# Laser_Array_CPU_V1_2.net
KiCad netlist of a schematic drawn in EAGLE
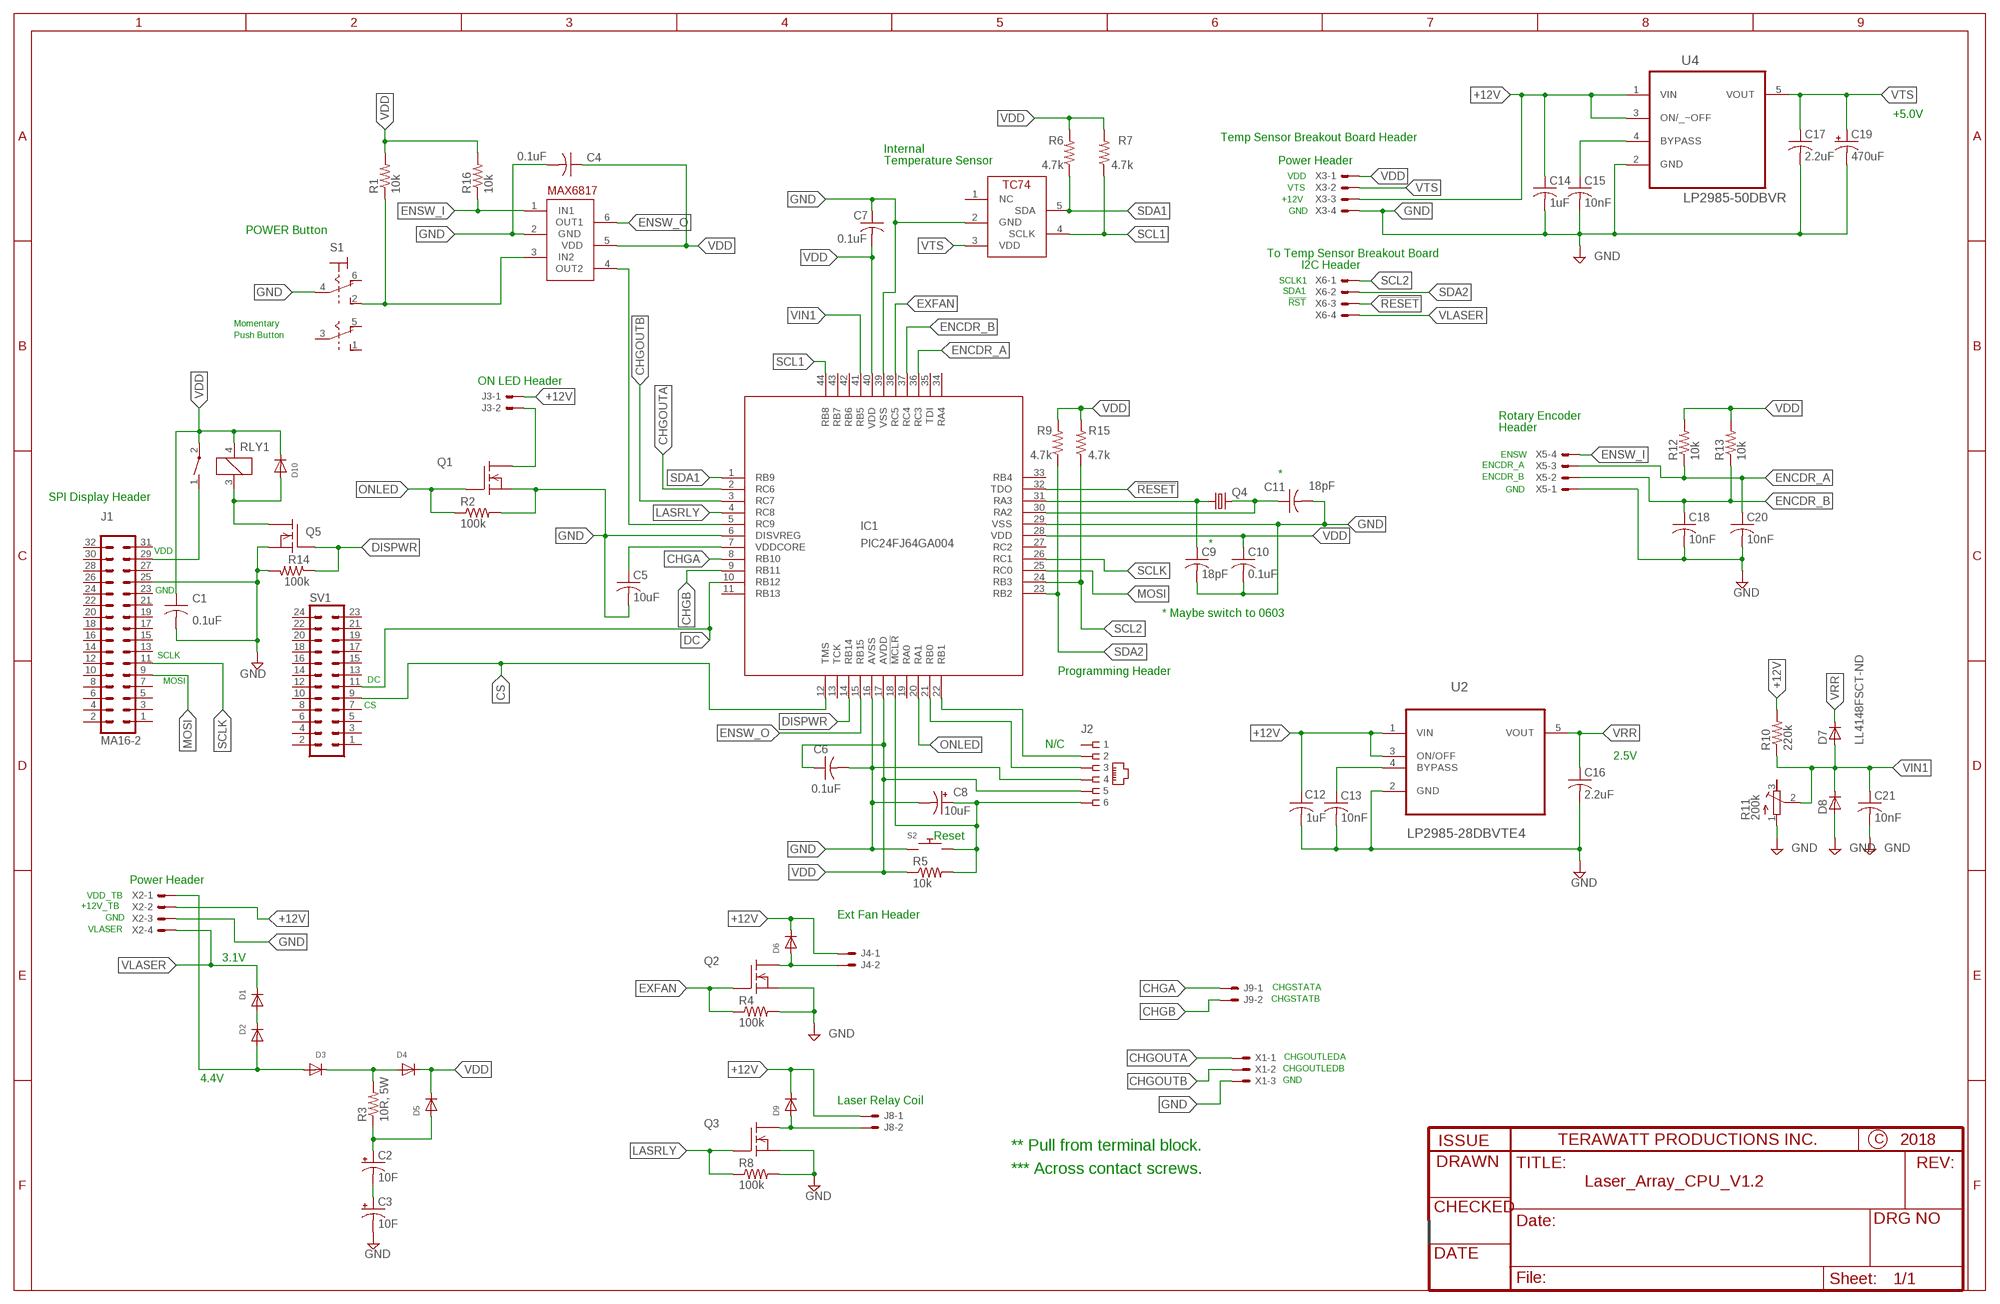
[diagram p0: schematic, sheet 1]

(export (version "E")
  (design (tool "Eeschema 10.0.6"))
  (components
    (comp (ref "C1")
      (value "0.1uF")
      (footprint "eagle-import:C0805")
      (libsource (lib "eagle-import") (part "C-USC0805"))
    )
    (comp (ref "C2")
      (value "10F")
      (footprint "eagle-import:E5-10,5")
      (libsource (lib "eagle-import") (part "CPOL-USE5-10.5"))
    )
    (comp (ref "C3")
      (value "10F")
      (footprint "eagle-import:E5-10,5")
      (libsource (lib "eagle-import") (part "CPOL-USE5-10.5"))
    )
    (comp (ref "C4")
      (value "0.1uF")
      (footprint "eagle-import:C0805")
      (libsource (lib "eagle-import") (part "C-USC0805"))
    )
    (comp (ref "C5")
      (value "10uF")
      (footprint "eagle-import:C0805")
      (libsource (lib "eagle-import") (part "C-USC0805"))
    )
    (comp (ref "C6")
      (value "0.1uF")
      (footprint "eagle-import:C0805")
      (libsource (lib "eagle-import") (part "C-USC0805"))
    )
    (comp (ref "C7")
      (value "0.1uF")
      (footprint "eagle-import:C0805")
      (libsource (lib "eagle-import") (part "C-USC0805"))
    )
    (comp (ref "C8")
      (value "10uF")
      (footprint "eagle-import:CAP3X3")
      (libsource (lib "eagle-import") (part "CAP3X3"))
    )
    (comp (ref "C9")
      (value "18pF")
      (footprint "eagle-import:C0805")
      (libsource (lib "eagle-import") (part "C-USC0805"))
    )
    (comp (ref "C10")
      (value "0.1uF")
      (footprint "eagle-import:C0805")
      (libsource (lib "eagle-import") (part "C-USC0805"))
    )
    (comp (ref "C11")
      (value "18pF")
      (footprint "eagle-import:C0805")
      (libsource (lib "eagle-import") (part "C-USC0805"))
    )
    (comp (ref "C12")
      (value "1uF")
      (footprint "eagle-import:C0805")
      (libsource (lib "eagle-import") (part "C-USC0805"))
    )
    (comp (ref "C13")
      (value "10nF")
      (footprint "eagle-import:C0805")
      (libsource (lib "eagle-import") (part "C-USC0805"))
    )
    (comp (ref "C14")
      (value "1uF")
      (footprint "eagle-import:C0805")
      (libsource (lib "eagle-import") (part "C-USC0805"))
    )
    (comp (ref "C15")
      (value "10nF")
      (footprint "eagle-import:C0805")
      (libsource (lib "eagle-import") (part "C-USC0805"))
    )
    (comp (ref "C16")
      (value "2.2uF")
      (footprint "eagle-import:C0805")
      (libsource (lib "eagle-import") (part "C-USC0805"))
    )
    (comp (ref "C17")
      (value "2.2uF")
      (footprint "eagle-import:C0805")
      (libsource (lib "eagle-import") (part "C-USC0805"))
    )
    (comp (ref "C18")
      (value "10nF")
      (footprint "eagle-import:C0805")
      (libsource (lib "eagle-import") (part "C-USC0805"))
    )
    (comp (ref "C19")
      (value "470uF")
      (footprint "eagle-import:PANASONIC_F")
      (libsource (lib "eagle-import") (part "CPOL-USF"))
    )
    (comp (ref "C20")
      (value "10nF")
      (footprint "eagle-import:C0805")
      (libsource (lib "eagle-import") (part "C-USC0805"))
    )
    (comp (ref "C21")
      (value "10nF")
      (footprint "eagle-import:C0805")
      (libsource (lib "eagle-import") (part "C-USC0805"))
    )
    (comp (ref "D1")
      (value "S10M-TPMSCT_ND")
      (footprint "eagle-import:S10M-TPMSCT-ND")
      (libsource (lib "eagle-import") (part "S10M-TPMSCT_ND"))
    )
    (comp (ref "D2")
      (value "S10M-TPMSCT_ND")
      (footprint "eagle-import:S10M-TPMSCT-ND")
      (libsource (lib "eagle-import") (part "S10M-TPMSCT_ND"))
    )
    (comp (ref "D3")
      (value "S10M-TPMSCT_ND")
      (footprint "eagle-import:S10M-TPMSCT-ND")
      (libsource (lib "eagle-import") (part "S10M-TPMSCT_ND"))
    )
    (comp (ref "D4")
      (value "DIODE_GENPURP_1A_100V")
      (footprint "eagle-import:DO214AC")
      (libsource (lib "eagle-import") (part "DIODE_GENPURP_1A_100V"))
    )
    (comp (ref "D5")
      (value "DIODE_GENPURP_1A_100V")
      (footprint "eagle-import:DO214AC")
      (libsource (lib "eagle-import") (part "DIODE_GENPURP_1A_100V"))
    )
    (comp (ref "D6")
      (value "DIODE_GENPURP_1A_100V")
      (footprint "eagle-import:DO214AC")
      (libsource (lib "eagle-import") (part "DIODE_GENPURP_1A_100V"))
    )
    (comp (ref "D7")
      (value "LL4148FSCT-ND")
      (footprint "eagle-import:SOD80")
      (libsource (lib "eagle-import") (part "D-SOD-80"))
    )
    (comp (ref "D8")
      (value "LL4148FSCT-ND")
      (footprint "eagle-import:SOD80")
      (libsource (lib "eagle-import") (part "D-SOD-80"))
    )
    (comp (ref "D9")
      (value "DIODE_GENPURP_1A_100V")
      (footprint "eagle-import:DO214AC")
      (libsource (lib "eagle-import") (part "DIODE_GENPURP_1A_100V"))
    )
    (comp (ref "D10")
      (value "DIODE_GENPURP_1A_100V")
      (footprint "eagle-import:DO214AC")
      (libsource (lib "eagle-import") (part "DIODE_GENPURP_1A_100V"))
    )
    (comp (ref "IC1")
      (value "PIC24FJ64GA004")
      (footprint "eagle-import:TQFP44")
      (fields (field (name "MPN") "PIC24FJ64GA004-E/PT"))
      (libsource (lib "eagle-import") (part "PIC24FJ64GA004"))
    )
    (comp (ref "J1")
      (value "MA16-2")
      (footprint "eagle-import:MA16-2")
      (libsource (lib "eagle-import") (part "MA16-2"))
    )
    (comp (ref "J2")
      (value "RJ_25")
      (footprint "eagle-import:RJ11-NO_SHIELD")
      (libsource (lib "eagle-import") (part "RJ_25"))
    )
    (comp (ref "J3")
      (value "22-23-2021")
      (footprint "eagle-import:22-23-2021")
      (fields (field (name "MF") "MOLEX"))
      (libsource (lib "eagle-import") (part "22-23-2021"))
    )
    (comp (ref "J4")
      (value "22-23-2021")
      (footprint "eagle-import:22-23-2021")
      (fields (field (name "MF") "MOLEX"))
      (libsource (lib "eagle-import") (part "22-23-2021"))
    )
    (comp (ref "J8")
      (value "22-23-2021")
      (footprint "eagle-import:22-23-2021")
      (fields (field (name "MF") "MOLEX"))
      (libsource (lib "eagle-import") (part "22-23-2021"))
    )
    (comp (ref "J9")
      (value "22-23-2021")
      (footprint "eagle-import:22-23-2021")
      (fields (field (name "MF") "MOLEX"))
      (libsource (lib "eagle-import") (part "22-23-2021"))
    )
    (comp (ref "Q1")
      (value "QS5U34CT-ND_MOSFET_N_CHANNEL")
      (footprint "eagle-import:SOT23-5L")
      (libsource (lib "eagle-import") (part "QS5U34CT-ND_MOSFET_N_CHANNEL"))
    )
    (comp (ref "Q2")
      (value "QS5U34CT-ND_MOSFET_N_CHANNEL")
      (footprint "eagle-import:SOT23-5L")
      (libsource (lib "eagle-import") (part "QS5U34CT-ND_MOSFET_N_CHANNEL"))
    )
    (comp (ref "Q3")
      (value "QS5U34CT-ND_MOSFET_N_CHANNEL")
      (footprint "eagle-import:SOT23-5L")
      (libsource (lib "eagle-import") (part "QS5U34CT-ND_MOSFET_N_CHANNEL"))
    )
    (comp (ref "Q4")
      (value "CRYSTALSM49")
      (footprint "eagle-import:SM49")
      (libsource (lib "eagle-import") (part "CRYSTALSM49"))
    )
    (comp (ref "Q5")
      (value "QS5U34CT-ND_MOSFET_N_CHANNEL")
      (footprint "eagle-import:SOT23-5L")
      (libsource (lib "eagle-import") (part "QS5U34CT-ND_MOSFET_N_CHANNEL"))
    )
    (comp (ref "R1")
      (value "10k")
      (footprint "eagle-import:R0805")
      (libsource (lib "eagle-import") (part "R-US_R0805"))
    )
    (comp (ref "R2")
      (value "100k")
      (footprint "eagle-import:R0805")
      (libsource (lib "eagle-import") (part "R-US_R0805"))
    )
    (comp (ref "R3")
      (value "10R, 5W")
      (footprint "eagle-import:RESISTOR5W")
      (libsource (lib "eagle-import") (part "RESISTOR5W"))
    )
    (comp (ref "R4")
      (value "100k")
      (footprint "eagle-import:R0805")
      (libsource (lib "eagle-import") (part "R-US_R0805"))
    )
    (comp (ref "R5")
      (value "10k")
      (footprint "eagle-import:R0805")
      (libsource (lib "eagle-import") (part "R-US_R0805"))
    )
    (comp (ref "R6")
      (value "4.7k")
      (footprint "eagle-import:M0805")
      (libsource (lib "eagle-import") (part "R-US_M0805"))
    )
    (comp (ref "R7")
      (value "4.7k")
      (footprint "eagle-import:M0805")
      (libsource (lib "eagle-import") (part "R-US_M0805"))
    )
    (comp (ref "R8")
      (value "100k")
      (footprint "eagle-import:R0805")
      (libsource (lib "eagle-import") (part "R-US_R0805"))
    )
    (comp (ref "R9")
      (value "4.7k")
      (footprint "eagle-import:M0805")
      (libsource (lib "eagle-import") (part "R-US_M0805"))
    )
    (comp (ref "R10")
      (value "220k")
      (footprint "eagle-import:M0805")
      (libsource (lib "eagle-import") (part "R-US_M0805"))
    )
    (comp (ref "R11")
      (value "200k")
      (footprint "eagle-import:RTRIM3224X")
      (libsource (lib "eagle-import") (part "R-TRIMM3224X"))
    )
    (comp (ref "R12")
      (value "10k")
      (footprint "eagle-import:M0805")
      (libsource (lib "eagle-import") (part "R-US_M0805"))
    )
    (comp (ref "R13")
      (value "10k")
      (footprint "eagle-import:M0805")
      (libsource (lib "eagle-import") (part "R-US_M0805"))
    )
    (comp (ref "R14")
      (value "100k")
      (footprint "eagle-import:R0805")
      (libsource (lib "eagle-import") (part "R-US_R0805"))
    )
    (comp (ref "R15")
      (value "4.7k")
      (footprint "eagle-import:M0805")
      (libsource (lib "eagle-import") (part "R-US_M0805"))
    )
    (comp (ref "R16")
      (value "10k")
      (footprint "eagle-import:R0805")
      (libsource (lib "eagle-import") (part "R-US_R0805"))
    )
    (comp (ref "RLY1")
      (value "RELAY_SPST_1A")
      (footprint "eagle-import:RELAY_SPST_1A")
      (libsource (lib "eagle-import") (part "RELAY_SPST_1A"))
    )
    (comp (ref "S1")
      (value "DPDT_TOGGLE")
      (footprint "eagle-import:22-23-2061")
      (libsource (lib "eagle-import") (part "DPDT_TOGGLE"))
    )
    (comp (ref "S2")
      (value "TACT_PB")
      (footprint "eagle-import:PUSHBUTTON_SMD_SJ")
      (libsource (lib "eagle-import") (part "TACT_PB"))
    )
    (comp (ref "S3")
      (value "TC74")
      (footprint "eagle-import:SOT23-5L")
      (libsource (lib "eagle-import") (part "TC74"))
    )
    (comp (ref "SV1")
      (value "MA12-2")
      (footprint "eagle-import:MA12-2")
      (libsource (lib "eagle-import") (part "MA12-2"))
    )
    (comp (ref "U1")
      (value "MAX6817")
      (footprint "eagle-import:SOT23-6")
      (libsource (lib "eagle-import") (part "MAX6817"))
    )
    (comp (ref "U2")
      (value "LP2985-28DBVTE4")
      (footprint "eagle-import:SOT95P280X145-5N")
      (libsource (lib "eagle-import") (part "LP2985-28DBVTE4"))
    )
    (comp (ref "U4")
      (value "LP2985-50DBVR")
      (footprint "eagle-import:SOT95P280X145-5N")
      (fields (field (name "MPN") "LP2985-33DBVT"))
      (libsource (lib "eagle-import") (part "LP2985-50DBVR"))
    )
    (comp (ref "X1")
      (value "22-23-2031")
      (footprint "eagle-import:22-23-2031")
      (fields (field (name "MF") "MOLEX"))
      (libsource (lib "eagle-import") (part "22-23-2031"))
    )
    (comp (ref "X2")
      (value "22-23-2041")
      (footprint "eagle-import:22-23-2041")
      (fields (field (name "MF") "MOLEX"))
      (libsource (lib "eagle-import") (part "22-23-2041"))
    )
    (comp (ref "X3")
      (value "22-23-2041")
      (footprint "eagle-import:22-23-2041")
      (fields (field (name "MF") "MOLEX"))
      (libsource (lib "eagle-import") (part "22-23-2041"))
    )
    (comp (ref "X5")
      (value "22-23-2041")
      (footprint "eagle-import:22-23-2041")
      (fields (field (name "MF") "MOLEX"))
      (libsource (lib "eagle-import") (part "22-23-2041"))
    )
    (comp (ref "X6")
      (value "22-23-2041")
      (footprint "eagle-import:22-23-2041")
      (fields (field (name "MF") "MOLEX"))
      (libsource (lib "eagle-import") (part "22-23-2041"))
    )
  )
  (nets
    (net (code "1") (name "+12V") (class "Default")
      (node (ref "C12") (pin "1") (pinfunction "1_1") (pintype "passive"))
      (node (ref "C14") (pin "1") (pinfunction "1_1") (pintype "passive"))
      (node (ref "D6") (pin "C") (pinfunction "C_C") (pintype "passive"))
      (node (ref "D9") (pin "C") (pinfunction "C_C") (pintype "passive"))
      (node (ref "J3") (pin "1") (pinfunction "S_1") (pintype "passive"))
      (node (ref "J4") (pin "1") (pinfunction "S_1") (pintype "passive"))
      (node (ref "J8") (pin "1") (pinfunction "S_1") (pintype "passive"))
      (node (ref "R10") (pin "2") (pinfunction "2_2") (pintype "passive"))
      (node (ref "U2") (pin "1") (pinfunction "VIN_1") (pintype "power_in"))
      (node (ref "U2") (pin "3") (pinfunction "ON/OFF_3") (pintype "input"))
      (node (ref "U4") (pin "1") (pinfunction "VIN_1") (pintype "power_in"))
      (node (ref "U4") (pin "3") (pinfunction "ON/_~{OFF}_3") (pintype "input"))
      (node (ref "X2") (pin "2") (pinfunction "S_2") (pintype "passive"))
      (node (ref "X3") (pin "3") (pinfunction "S_3") (pintype "passive"))
    )
    (net (code "2") (name "/~{RESET}") (class "Default")
      (node (ref "IC1") (pin "32") (pinfunction "TDO_32") (pintype "output"))
      (node (ref "X6") (pin "3") (pinfunction "S_3") (pintype "passive"))
    )
    (net (code "3") (name "CHGA") (class "Default")
      (node (ref "IC1") (pin "8") (pinfunction "RB10_8") (pintype "bidirectional"))
      (node (ref "J9") (pin "1") (pinfunction "S_1") (pintype "passive"))
    )
    (net (code "4") (name "CHGB") (class "Default")
      (node (ref "IC1") (pin "9") (pinfunction "RB11_9") (pintype "bidirectional"))
      (node (ref "J9") (pin "2") (pinfunction "S_2") (pintype "passive"))
    )
    (net (code "5") (name "CHGOUTA") (class "Default")
      (node (ref "IC1") (pin "2") (pinfunction "RC6_2") (pintype "bidirectional"))
      (node (ref "X1") (pin "1") (pinfunction "S_1") (pintype "passive"))
    )
    (net (code "6") (name "CHGOUTB") (class "Default")
      (node (ref "IC1") (pin "3") (pinfunction "RC7_3") (pintype "bidirectional"))
      (node (ref "X1") (pin "2") (pinfunction "S_2") (pintype "passive"))
    )
    (net (code "7") (name "CS") (class "Default")
      (node (ref "IC1") (pin "12") (pinfunction "TMS_12") (pintype "input"))
      (node (ref "SV1") (pin "9") (pinfunction "9_9") (pintype "passive"))
    )
    (net (code "8") (name "DC") (class "Default")
      (node (ref "IC1") (pin "10") (pinfunction "RB12_10") (pintype "bidirectional"))
      (node (ref "SV1") (pin "11") (pinfunction "11_11") (pintype "passive"))
    )
    (net (code "9") (name "DISPWR") (class "Default")
      (node (ref "IC1") (pin "14") (pinfunction "RB14_14") (pintype "bidirectional"))
      (node (ref "Q5") (pin "1") (pinfunction "G_1") (pintype "passive"))
      (node (ref "R14") (pin "1") (pinfunction "1_1") (pintype "passive"))
    )
    (net (code "10") (name "ENCDR_A") (class "Default")
      (node (ref "C20") (pin "1") (pinfunction "1_1") (pintype "passive"))
      (node (ref "IC1") (pin "36") (pinfunction "RC3_36") (pintype "bidirectional"))
      (node (ref "R12") (pin "1") (pinfunction "1_1") (pintype "passive"))
      (node (ref "X5") (pin "3") (pinfunction "S_3") (pintype "passive"))
    )
    (net (code "11") (name "ENCDR_B") (class "Default")
      (node (ref "C18") (pin "1") (pinfunction "1_1") (pintype "passive"))
      (node (ref "IC1") (pin "37") (pinfunction "RC4_37") (pintype "bidirectional"))
      (node (ref "R13") (pin "1") (pinfunction "1_1") (pintype "passive"))
      (node (ref "X5") (pin "2") (pinfunction "S_2") (pintype "passive"))
    )
    (net (code "12") (name "ENSW_I") (class "Default")
      (node (ref "R16") (pin "1") (pinfunction "1_1") (pintype "passive"))
      (node (ref "U1") (pin "1") (pinfunction "IN1_1") (pintype "input"))
      (node (ref "X5") (pin "4") (pinfunction "S_4") (pintype "passive"))
    )
    (net (code "13") (name "ENSW_O") (class "Default")
      (node (ref "IC1") (pin "15") (pinfunction "RB15_15") (pintype "bidirectional"))
      (node (ref "U1") (pin "6") (pinfunction "OUT1_6") (pintype "output"))
    )
    (net (code "14") (name "EXFAN") (class "Default")
      (node (ref "IC1") (pin "38") (pinfunction "RC5_38") (pintype "bidirectional"))
      (node (ref "Q2") (pin "1") (pinfunction "G_1") (pintype "passive"))
      (node (ref "R4") (pin "1") (pinfunction "1_1") (pintype "passive"))
    )
    (net (code "15") (name "GND") (class "Default")
      (node (ref "C1") (pin "2") (pinfunction "2_2") (pintype "passive"))
      (node (ref "C10") (pin "2") (pinfunction "2_2") (pintype "passive"))
      (node (ref "C11") (pin "2") (pinfunction "2_2") (pintype "passive"))
      (node (ref "C12") (pin "2") (pinfunction "2_2") (pintype "passive"))
      (node (ref "C13") (pin "2") (pinfunction "2_2") (pintype "passive"))
      (node (ref "C14") (pin "2") (pinfunction "2_2") (pintype "passive"))
      (node (ref "C15") (pin "2") (pinfunction "2_2") (pintype "passive"))
      (node (ref "C16") (pin "2") (pinfunction "2_2") (pintype "passive"))
      (node (ref "C17") (pin "2") (pinfunction "2_2") (pintype "passive"))
      (node (ref "C18") (pin "2") (pinfunction "2_2") (pintype "passive"))
      (node (ref "C19") (pin "-") (pinfunction "-_-") (pintype "passive"))
      (node (ref "C20") (pin "2") (pinfunction "2_2") (pintype "passive"))
      (node (ref "C21") (pin "2") (pinfunction "2_2") (pintype "passive"))
      (node (ref "C3") (pin "-") (pinfunction "-_-") (pintype "passive"))
      (node (ref "C4") (pin "2") (pinfunction "2_2") (pintype "passive"))
      (node (ref "C5") (pin "2") (pinfunction "2_2") (pintype "passive"))
      (node (ref "C6") (pin "2") (pinfunction "2_2") (pintype "passive"))
      (node (ref "C7") (pin "1") (pinfunction "1_1") (pintype "passive"))
      (node (ref "C8") (pin "-") (pinfunction "-_-") (pintype "passive"))
      (node (ref "C9") (pin "2") (pinfunction "2_2") (pintype "passive"))
      (node (ref "D8") (pin "2") (pinfunction "A_2") (pintype "passive"))
      (node (ref "IC1") (pin "16") (pinfunction "AVSS_16") (pintype "power_in"))
      (node (ref "IC1") (pin "29") (pinfunction "VSS_29") (pintype "power_in"))
      (node (ref "IC1") (pin "39") (pinfunction "VSS_39") (pintype "power_in"))
      (node (ref "IC1") (pin "6") (pinfunction "DISVREG_6") (pintype "passive"))
      (node (ref "J1") (pin "25") (pinfunction "25_25") (pintype "passive"))
      (node (ref "J2") (pin "4") (pinfunction "4_4") (pintype "passive"))
      (node (ref "Q1") (pin "2") (pinfunction "S_2") (pintype "passive"))
      (node (ref "Q2") (pin "2") (pinfunction "S_2") (pintype "passive"))
      (node (ref "Q3") (pin "2") (pinfunction "S_2") (pintype "passive"))
      (node (ref "Q5") (pin "2") (pinfunction "S_2") (pintype "passive"))
      (node (ref "R11") (pin "1") (pinfunction "A_1") (pintype "passive"))
      (node (ref "R14") (pin "2") (pinfunction "2_2") (pintype "passive"))
      (node (ref "R2") (pin "2") (pinfunction "2_2") (pintype "passive"))
      (node (ref "R4") (pin "2") (pinfunction "2_2") (pintype "passive"))
      (node (ref "R8") (pin "2") (pinfunction "2_2") (pintype "passive"))
      (node (ref "S1") (pin "4") (pinfunction "P_4") (pintype "passive"))
      (node (ref "S2") (pin "1") (pinfunction "1_1") (pintype "passive"))
      (node (ref "S2") (pin "2") (pinfunction "1_2") (pintype "passive"))
      (node (ref "S3") (pin "2") (pinfunction "GND_2") (pintype "bidirectional"))
      (node (ref "U1") (pin "2") (pinfunction "GND_2") (pintype "power_in"))
      (node (ref "U2") (pin "2") (pinfunction "GND_2") (pintype "passive"))
      (node (ref "U4") (pin "2") (pinfunction "GND_2") (pintype "passive"))
      (node (ref "X1") (pin "3") (pinfunction "S_3") (pintype "passive"))
      (node (ref "X2") (pin "3") (pinfunction "S_3") (pintype "passive"))
      (node (ref "X3") (pin "4") (pinfunction "S_4") (pintype "passive"))
      (node (ref "X5") (pin "1") (pinfunction "S_1") (pintype "passive"))
    )
    (net (code "16") (name "LASRLY") (class "Default")
      (node (ref "IC1") (pin "4") (pinfunction "RC8_4") (pintype "bidirectional"))
      (node (ref "Q3") (pin "1") (pinfunction "G_1") (pintype "passive"))
      (node (ref "R8") (pin "1") (pinfunction "1_1") (pintype "passive"))
    )
    (net (code "17") (name "MOSI") (class "Default")
      (node (ref "IC1") (pin "25") (pinfunction "RC0_25") (pintype "bidirectional"))
      (node (ref "J1") (pin "9") (pinfunction "9_9") (pintype "passive"))
    )
    (net (code "18") (name "Net-(C2-Pad+)") (class "Default")
      (node (ref "C2") (pin "+") (pinfunction "+_+") (pintype "passive"))
      (node (ref "D5") (pin "A") (pinfunction "A_A") (pintype "passive"))
      (node (ref "R3") (pin "1") (pinfunction "1_1") (pintype "passive"))
    )
    (net (code "19") (name "Net-(C2-Pad-)") (class "Default")
      (node (ref "C2") (pin "-") (pinfunction "-_-") (pintype "passive"))
      (node (ref "C3") (pin "+") (pinfunction "+_+") (pintype "passive"))
    )
    (net (code "20") (name "Net-(D1-PadA)") (class "Default")
      (node (ref "D1") (pin "A") (pinfunction "A_A") (pintype "passive"))
      (node (ref "D2") (pin "C") (pinfunction "C_C") (pintype "passive"))
    )
    (net (code "21") (name "Net-(D3-PadC)") (class "Default")
      (node (ref "D3") (pin "C") (pinfunction "C_C") (pintype "passive"))
      (node (ref "D4") (pin "A") (pinfunction "A_A") (pintype "passive"))
      (node (ref "R3") (pin "2") (pinfunction "2_2") (pintype "passive"))
    )
    (net (code "22") (name "Net-(IC1-RA2)") (class "Default")
      (node (ref "C11") (pin "1") (pinfunction "1_1") (pintype "passive"))
      (node (ref "IC1") (pin "30") (pinfunction "RA2_30") (pintype "bidirectional"))
      (node (ref "Q4") (pin "2") (pinfunction "2_2") (pintype "passive"))
    )
    (net (code "23") (name "Net-(IC1-RA3)") (class "Default")
      (node (ref "C9") (pin "1") (pinfunction "1_1") (pintype "passive"))
      (node (ref "IC1") (pin "31") (pinfunction "RA3_31") (pintype "bidirectional"))
      (node (ref "Q4") (pin "1") (pinfunction "1_1") (pintype "passive"))
    )
    (net (code "24") (name "Net-(IC1-RB0)") (class "Default")
      (node (ref "IC1") (pin "21") (pinfunction "RB0_21") (pintype "bidirectional"))
      (node (ref "J2") (pin "3") (pinfunction "3_3") (pintype "passive"))
    )
    (net (code "25") (name "Net-(IC1-RB1)") (class "Default")
      (node (ref "IC1") (pin "22") (pinfunction "RB1_22") (pintype "bidirectional"))
      (node (ref "J2") (pin "2") (pinfunction "2_2") (pintype "passive"))
    )
    (net (code "26") (name "Net-(IC1-RC9)") (class "Default")
      (node (ref "IC1") (pin "5") (pinfunction "RC9_5") (pintype "bidirectional"))
      (node (ref "U1") (pin "4") (pinfunction "OUT2_4") (pintype "output"))
    )
    (net (code "27") (name "Net-(IC1-VDDCORE)") (class "Default")
      (node (ref "C5") (pin "1") (pinfunction "1_1") (pintype "passive"))
      (node (ref "IC1") (pin "7") (pinfunction "VDDCORE_7") (pintype "power_in"))
    )
    (net (code "28") (name "Net-(IC1-~{MCLR})") (class "Default")
      (node (ref "C8") (pin "+") (pinfunction "+_+") (pintype "passive"))
      (node (ref "IC1") (pin "18") (pinfunction "~{MCLR}_18") (pintype "bidirectional"))
      (node (ref "J2") (pin "6") (pinfunction "6_6") (pintype "passive"))
      (node (ref "R5") (pin "2") (pinfunction "2_2") (pintype "passive"))
      (node (ref "S2") (pin "3") (pinfunction "2_3") (pintype "passive"))
      (node (ref "S2") (pin "4") (pinfunction "2_4") (pintype "passive"))
    )
    (net (code "29") (name "Net-(J3B-S)") (class "Default")
      (node (ref "J3") (pin "2") (pinfunction "S_2") (pintype "passive"))
      (node (ref "Q1") (pin "5") (pinfunction "D_5") (pintype "passive"))
    )
    (net (code "30") (name "Net-(J4B-S)") (class "Default")
      (node (ref "D6") (pin "A") (pinfunction "A_A") (pintype "passive"))
      (node (ref "J4") (pin "2") (pinfunction "S_2") (pintype "passive"))
      (node (ref "Q2") (pin "5") (pinfunction "D_5") (pintype "passive"))
    )
    (net (code "31") (name "Net-(J8B-S)") (class "Default")
      (node (ref "D9") (pin "A") (pinfunction "A_A") (pintype "passive"))
      (node (ref "J8") (pin "2") (pinfunction "S_2") (pintype "passive"))
      (node (ref "Q3") (pin "5") (pinfunction "D_5") (pintype "passive"))
    )
    (net (code "32") (name "Net-(Q5-D)") (class "Default")
      (node (ref "D10") (pin "A") (pinfunction "A_A") (pintype "passive"))
      (node (ref "Q5") (pin "5") (pinfunction "D_5") (pintype "passive"))
      (node (ref "RLY1") (pin "3") (pinfunction "1_3") (pintype "passive"))
    )
    (net (code "33") (name "Net-(RLY1B-S)") (class "Default")
      (node (ref "J1") (pin "29") (pinfunction "29_29") (pintype "passive"))
      (node (ref "RLY1") (pin "1") (pinfunction "S_1") (pintype "passive"))
    )
    (net (code "34") (name "Net-(S1-S)") (class "Default")
      (node (ref "R1") (pin "1") (pinfunction "1_1") (pintype "passive"))
      (node (ref "S1") (pin "2") (pinfunction "S_2") (pintype "passive"))
      (node (ref "U1") (pin "3") (pinfunction "IN2_3") (pintype "input"))
    )
    (net (code "35") (name "Net-(U2-BYPASS)") (class "Default")
      (node (ref "C13") (pin "1") (pinfunction "1_1") (pintype "passive"))
      (node (ref "U2") (pin "4") (pinfunction "BYPASS_4") (pintype "input"))
    )
    (net (code "36") (name "Net-(U4-BYPASS)") (class "Default")
      (node (ref "C15") (pin "1") (pinfunction "1_1") (pintype "passive"))
      (node (ref "U4") (pin "4") (pinfunction "BYPASS_4") (pintype "input"))
    )
    (net (code "37") (name "Net-(X2A-S)") (class "Default")
      (node (ref "D2") (pin "A") (pinfunction "A_A") (pintype "passive"))
      (node (ref "D3") (pin "A") (pinfunction "A_A") (pintype "passive"))
      (node (ref "X2") (pin "1") (pinfunction "S_1") (pintype "passive"))
    )
    (net (code "38") (name "ONLED") (class "Default")
      (node (ref "IC1") (pin "20") (pinfunction "RA1_20") (pintype "bidirectional"))
      (node (ref "Q1") (pin "1") (pinfunction "G_1") (pintype "passive"))
      (node (ref "R2") (pin "1") (pinfunction "1_1") (pintype "passive"))
    )
    (net (code "39") (name "SCL1") (class "Default")
      (node (ref "IC1") (pin "44") (pinfunction "RB8_44") (pintype "bidirectional"))
      (node (ref "R7") (pin "1") (pinfunction "1_1") (pintype "passive"))
      (node (ref "S3") (pin "4") (pinfunction "SCLK_4") (pintype "bidirectional"))
    )
    (net (code "40") (name "SCL2") (class "Default")
      (node (ref "IC1") (pin "24") (pinfunction "RB3_24") (pintype "bidirectional"))
      (node (ref "R15") (pin "1") (pinfunction "1_1") (pintype "passive"))
      (node (ref "X6") (pin "1") (pinfunction "S_1") (pintype "passive"))
    )
    (net (code "41") (name "SCLK") (class "Default")
      (node (ref "IC1") (pin "26") (pinfunction "RC1_26") (pintype "bidirectional"))
      (node (ref "J1") (pin "11") (pinfunction "11_11") (pintype "passive"))
    )
    (net (code "42") (name "SDA1") (class "Default")
      (node (ref "IC1") (pin "1") (pinfunction "RB9_1") (pintype "bidirectional"))
      (node (ref "R6") (pin "1") (pinfunction "1_1") (pintype "passive"))
      (node (ref "S3") (pin "5") (pinfunction "SDA_5") (pintype "bidirectional"))
    )
    (net (code "43") (name "SDA2") (class "Default")
      (node (ref "IC1") (pin "23") (pinfunction "RB2_23") (pintype "bidirectional"))
      (node (ref "R9") (pin "1") (pinfunction "1_1") (pintype "passive"))
      (node (ref "X6") (pin "2") (pinfunction "S_2") (pintype "passive"))
    )
    (net (code "44") (name "VDD") (class "Default")
      (node (ref "C1") (pin "1") (pinfunction "1_1") (pintype "passive"))
      (node (ref "C10") (pin "1") (pinfunction "1_1") (pintype "passive"))
      (node (ref "C4") (pin "1") (pinfunction "1_1") (pintype "passive"))
      (node (ref "C6") (pin "1") (pinfunction "1_1") (pintype "passive"))
      (node (ref "C7") (pin "2") (pinfunction "2_2") (pintype "passive"))
      (node (ref "D10") (pin "C") (pinfunction "C_C") (pintype "passive"))
      (node (ref "D4") (pin "C") (pinfunction "C_C") (pintype "passive"))
      (node (ref "D5") (pin "C") (pinfunction "C_C") (pintype "passive"))
      (node (ref "IC1") (pin "17") (pinfunction "AVDD_17") (pintype "power_in"))
      (node (ref "IC1") (pin "28") (pinfunction "VDD_28") (pintype "power_in"))
      (node (ref "IC1") (pin "40") (pinfunction "VDD_40") (pintype "power_in"))
      (node (ref "J2") (pin "5") (pinfunction "5_5") (pintype "passive"))
      (node (ref "R1") (pin "2") (pinfunction "2_2") (pintype "passive"))
      (node (ref "R12") (pin "2") (pinfunction "2_2") (pintype "passive"))
      (node (ref "R13") (pin "2") (pinfunction "2_2") (pintype "passive"))
      (node (ref "R15") (pin "2") (pinfunction "2_2") (pintype "passive"))
      (node (ref "R16") (pin "2") (pinfunction "2_2") (pintype "passive"))
      (node (ref "R5") (pin "1") (pinfunction "1_1") (pintype "passive"))
      (node (ref "R6") (pin "2") (pinfunction "2_2") (pintype "passive"))
      (node (ref "R7") (pin "2") (pinfunction "2_2") (pintype "passive"))
      (node (ref "R9") (pin "2") (pinfunction "2_2") (pintype "passive"))
      (node (ref "RLY1") (pin "2") (pinfunction "P_2") (pintype "passive"))
      (node (ref "RLY1") (pin "4") (pinfunction "2_4") (pintype "passive"))
      (node (ref "U1") (pin "5") (pinfunction "VDD_5") (pintype "power_in"))
      (node (ref "X3") (pin "1") (pinfunction "S_1") (pintype "passive"))
    )
    (net (code "45") (name "VIN1") (class "Default")
      (node (ref "C21") (pin "1") (pinfunction "1_1") (pintype "passive"))
      (node (ref "D7") (pin "2") (pinfunction "A_2") (pintype "passive"))
      (node (ref "D8") (pin "1") (pinfunction "C_1") (pintype "passive"))
      (node (ref "IC1") (pin "41") (pinfunction "RB5_41") (pintype "bidirectional"))
      (node (ref "R10") (pin "1") (pinfunction "1_1") (pintype "passive"))
      (node (ref "R11") (pin "2") (pinfunction "S_2") (pintype "passive"))
    )
    (net (code "46") (name "VLASER") (class "Default")
      (node (ref "D1") (pin "C") (pinfunction "C_C") (pintype "passive"))
      (node (ref "X2") (pin "4") (pinfunction "S_4") (pintype "passive"))
      (node (ref "X6") (pin "4") (pinfunction "S_4") (pintype "passive"))
    )
    (net (code "47") (name "VRR") (class "Default")
      (node (ref "C16") (pin "1") (pinfunction "1_1") (pintype "passive"))
      (node (ref "D7") (pin "1") (pinfunction "C_1") (pintype "passive"))
      (node (ref "U2") (pin "5") (pinfunction "VOUT_5") (pintype "output"))
    )
    (net (code "48") (name "VTS") (class "Default")
      (node (ref "C17") (pin "1") (pinfunction "1_1") (pintype "passive"))
      (node (ref "C19") (pin "+") (pinfunction "+_+") (pintype "passive"))
      (node (ref "S3") (pin "3") (pinfunction "VDD_3") (pintype "bidirectional"))
      (node (ref "U4") (pin "5") (pinfunction "VOUT_5") (pintype "output"))
      (node (ref "X3") (pin "2") (pinfunction "S_2") (pintype "passive"))
    )
    (net (code "49") (name "unconnected-(IC1-RA0-Pad19)") (class "Default")
      (node (ref "IC1") (pin "19") (pinfunction "RA0_19") (pintype "bidirectional"))
    )
    (net (code "50") (name "unconnected-(IC1-RA4-Pad34)") (class "Default")
      (node (ref "IC1") (pin "34") (pinfunction "RA4_34") (pintype "bidirectional"))
    )
    (net (code "51") (name "unconnected-(IC1-RB4-Pad33)") (class "Default")
      (node (ref "IC1") (pin "33") (pinfunction "RB4_33") (pintype "bidirectional"))
    )
    (net (code "52") (name "unconnected-(IC1-RB6-Pad42)") (class "Default")
      (node (ref "IC1") (pin "42") (pinfunction "RB6_42") (pintype "bidirectional"))
    )
    (net (code "53") (name "unconnected-(IC1-RB7-Pad43)") (class "Default")
      (node (ref "IC1") (pin "43") (pinfunction "RB7_43") (pintype "bidirectional"))
    )
    (net (code "54") (name "unconnected-(IC1-RB13-Pad11)") (class "Default")
      (node (ref "IC1") (pin "11") (pinfunction "RB13_11") (pintype "bidirectional"))
    )
    (net (code "55") (name "unconnected-(IC1-RC2-Pad27)") (class "Default")
      (node (ref "IC1") (pin "27") (pinfunction "RC2_27") (pintype "bidirectional"))
    )
    (net (code "56") (name "unconnected-(IC1-TCK-Pad13)") (class "Default")
      (node (ref "IC1") (pin "13") (pinfunction "TCK_13") (pintype "input"))
    )
    (net (code "57") (name "unconnected-(IC1-TDI-Pad35)") (class "Default")
      (node (ref "IC1") (pin "35") (pinfunction "TDI_35") (pintype "input"))
    )
    (net (code "58") (name "unconnected-(J1-Pad1)") (class "Default")
      (node (ref "J1") (pin "1") (pinfunction "1_1") (pintype "passive"))
    )
    (net (code "59") (name "unconnected-(J1-Pad2)") (class "Default")
      (node (ref "J1") (pin "2") (pinfunction "2_2") (pintype "passive"))
    )
    (net (code "60") (name "unconnected-(J1-Pad3)") (class "Default")
      (node (ref "J1") (pin "3") (pinfunction "3_3") (pintype "passive"))
    )
    (net (code "61") (name "unconnected-(J1-Pad4)") (class "Default")
      (node (ref "J1") (pin "4") (pinfunction "4_4") (pintype "passive"))
    )
    (net (code "62") (name "unconnected-(J1-Pad5)") (class "Default")
      (node (ref "J1") (pin "5") (pinfunction "5_5") (pintype "passive"))
    )
    (net (code "63") (name "unconnected-(J1-Pad6)") (class "Default")
      (node (ref "J1") (pin "6") (pinfunction "6_6") (pintype "passive"))
    )
    (net (code "64") (name "unconnected-(J1-Pad7)") (class "Default")
      (node (ref "J1") (pin "7") (pinfunction "7_7") (pintype "passive"))
    )
    (net (code "65") (name "unconnected-(J1-Pad8)") (class "Default")
      (node (ref "J1") (pin "8") (pinfunction "8_8") (pintype "passive"))
    )
    (net (code "66") (name "unconnected-(J1-Pad10)") (class "Default")
      (node (ref "J1") (pin "10") (pinfunction "10_10") (pintype "passive"))
    )
    (net (code "67") (name "unconnected-(J1-Pad12)") (class "Default")
      (node (ref "J1") (pin "12") (pinfunction "12_12") (pintype "passive"))
    )
    (net (code "68") (name "unconnected-(J1-Pad13)") (class "Default")
      (node (ref "J1") (pin "13") (pinfunction "13_13") (pintype "passive"))
    )
    (net (code "69") (name "unconnected-(J1-Pad14)") (class "Default")
      (node (ref "J1") (pin "14") (pinfunction "14_14") (pintype "passive"))
    )
    (net (code "70") (name "unconnected-(J1-Pad15)") (class "Default")
      (node (ref "J1") (pin "15") (pinfunction "15_15") (pintype "passive"))
    )
    (net (code "71") (name "unconnected-(J1-Pad16)") (class "Default")
      (node (ref "J1") (pin "16") (pinfunction "16_16") (pintype "passive"))
    )
    (net (code "72") (name "unconnected-(J1-Pad17)") (class "Default")
      (node (ref "J1") (pin "17") (pinfunction "17_17") (pintype "passive"))
    )
    (net (code "73") (name "unconnected-(J1-Pad18)") (class "Default")
      (node (ref "J1") (pin "18") (pinfunction "18_18") (pintype "passive"))
    )
    (net (code "74") (name "unconnected-(J1-Pad19)") (class "Default")
      (node (ref "J1") (pin "19") (pinfunction "19_19") (pintype "passive"))
    )
    (net (code "75") (name "unconnected-(J1-Pad20)") (class "Default")
      (node (ref "J1") (pin "20") (pinfunction "20_20") (pintype "passive"))
    )
    (net (code "76") (name "unconnected-(J1-Pad21)") (class "Default")
      (node (ref "J1") (pin "21") (pinfunction "21_21") (pintype "passive"))
    )
    (net (code "77") (name "unconnected-(J1-Pad22)") (class "Default")
      (node (ref "J1") (pin "22") (pinfunction "22_22") (pintype "passive"))
    )
    (net (code "78") (name "unconnected-(J1-Pad23)") (class "Default")
      (node (ref "J1") (pin "23") (pinfunction "23_23") (pintype "passive"))
    )
    (net (code "79") (name "unconnected-(J1-Pad24)") (class "Default")
      (node (ref "J1") (pin "24") (pinfunction "24_24") (pintype "passive"))
    )
    (net (code "80") (name "unconnected-(J1-Pad26)") (class "Default")
      (node (ref "J1") (pin "26") (pinfunction "26_26") (pintype "passive"))
    )
    (net (code "81") (name "unconnected-(J1-Pad27)") (class "Default")
      (node (ref "J1") (pin "27") (pinfunction "27_27") (pintype "passive"))
    )
    (net (code "82") (name "unconnected-(J1-Pad28)") (class "Default")
      (node (ref "J1") (pin "28") (pinfunction "28_28") (pintype "passive"))
    )
    (net (code "83") (name "unconnected-(J1-Pad30)") (class "Default")
      (node (ref "J1") (pin "30") (pinfunction "30_30") (pintype "passive"))
    )
    (net (code "84") (name "unconnected-(J1-Pad31)") (class "Default")
      (node (ref "J1") (pin "31") (pinfunction "31_31") (pintype "passive"))
    )
    (net (code "85") (name "unconnected-(J1-Pad32)") (class "Default")
      (node (ref "J1") (pin "32") (pinfunction "32_32") (pintype "passive"))
    )
    (net (code "86") (name "unconnected-(J2-Pad1)") (class "Default")
      (node (ref "J2") (pin "1") (pinfunction "1_1") (pintype "passive"))
    )
    (net (code "87") (name "unconnected-(R11-E-Pad3)") (class "Default")
      (node (ref "R11") (pin "3") (pinfunction "E_3") (pintype "passive"))
    )
    (net (code "88") (name "unconnected-(S1-O-Pad6)") (class "Default")
      (node (ref "S1") (pin "6") (pinfunction "O_6") (pintype "passive"))
    )
    (net (code "89") (name "unconnected-(S1-O1-Pad5)") (class "Default")
      (node (ref "S1") (pin "5") (pinfunction "O1_5") (pintype "passive"))
    )
    (net (code "90") (name "unconnected-(S1-P1-Pad3)") (class "Default")
      (node (ref "S1") (pin "3") (pinfunction "P1_3") (pintype "passive"))
    )
    (net (code "91") (name "unconnected-(S1-S1-Pad1)") (class "Default")
      (node (ref "S1") (pin "1") (pinfunction "S1_1") (pintype "passive"))
    )
    (net (code "92") (name "unconnected-(S3-NC-Pad1)") (class "Default")
      (node (ref "S3") (pin "1") (pinfunction "NC_1") (pintype "bidirectional"))
    )
    (net (code "93") (name "unconnected-(SV1-Pad1)") (class "Default")
      (node (ref "SV1") (pin "1") (pinfunction "1_1") (pintype "passive"))
    )
    (net (code "94") (name "unconnected-(SV1-Pad2)") (class "Default")
      (node (ref "SV1") (pin "2") (pinfunction "2_2") (pintype "passive"))
    )
    (net (code "95") (name "unconnected-(SV1-Pad3)") (class "Default")
      (node (ref "SV1") (pin "3") (pinfunction "3_3") (pintype "passive"))
    )
    (net (code "96") (name "unconnected-(SV1-Pad4)") (class "Default")
      (node (ref "SV1") (pin "4") (pinfunction "4_4") (pintype "passive"))
    )
    (net (code "97") (name "unconnected-(SV1-Pad5)") (class "Default")
      (node (ref "SV1") (pin "5") (pinfunction "5_5") (pintype "passive"))
    )
    (net (code "98") (name "unconnected-(SV1-Pad6)") (class "Default")
      (node (ref "SV1") (pin "6") (pinfunction "6_6") (pintype "passive"))
    )
    (net (code "99") (name "unconnected-(SV1-Pad7)") (class "Default")
      (node (ref "SV1") (pin "7") (pinfunction "7_7") (pintype "passive"))
    )
    (net (code "100") (name "unconnected-(SV1-Pad8)") (class "Default")
      (node (ref "SV1") (pin "8") (pinfunction "8_8") (pintype "passive"))
    )
    (net (code "101") (name "unconnected-(SV1-Pad10)") (class "Default")
      (node (ref "SV1") (pin "10") (pinfunction "10_10") (pintype "passive"))
    )
    (net (code "102") (name "unconnected-(SV1-Pad12)") (class "Default")
      (node (ref "SV1") (pin "12") (pinfunction "12_12") (pintype "passive"))
    )
    (net (code "103") (name "unconnected-(SV1-Pad13)") (class "Default")
      (node (ref "SV1") (pin "13") (pinfunction "13_13") (pintype "passive"))
    )
    (net (code "104") (name "unconnected-(SV1-Pad14)") (class "Default")
      (node (ref "SV1") (pin "14") (pinfunction "14_14") (pintype "passive"))
    )
    (net (code "105") (name "unconnected-(SV1-Pad15)") (class "Default")
      (node (ref "SV1") (pin "15") (pinfunction "15_15") (pintype "passive"))
    )
    (net (code "106") (name "unconnected-(SV1-Pad16)") (class "Default")
      (node (ref "SV1") (pin "16") (pinfunction "16_16") (pintype "passive"))
    )
    (net (code "107") (name "unconnected-(SV1-Pad17)") (class "Default")
      (node (ref "SV1") (pin "17") (pinfunction "17_17") (pintype "passive"))
    )
    (net (code "108") (name "unconnected-(SV1-Pad18)") (class "Default")
      (node (ref "SV1") (pin "18") (pinfunction "18_18") (pintype "passive"))
    )
    (net (code "109") (name "unconnected-(SV1-Pad19)") (class "Default")
      (node (ref "SV1") (pin "19") (pinfunction "19_19") (pintype "passive"))
    )
    (net (code "110") (name "unconnected-(SV1-Pad20)") (class "Default")
      (node (ref "SV1") (pin "20") (pinfunction "20_20") (pintype "passive"))
    )
    (net (code "111") (name "unconnected-(SV1-Pad21)") (class "Default")
      (node (ref "SV1") (pin "21") (pinfunction "21_21") (pintype "passive"))
    )
    (net (code "112") (name "unconnected-(SV1-Pad22)") (class "Default")
      (node (ref "SV1") (pin "22") (pinfunction "22_22") (pintype "passive"))
    )
    (net (code "113") (name "unconnected-(SV1-Pad23)") (class "Default")
      (node (ref "SV1") (pin "23") (pinfunction "23_23") (pintype "passive"))
    )
    (net (code "114") (name "unconnected-(SV1-Pad24)") (class "Default")
      (node (ref "SV1") (pin "24") (pinfunction "24_24") (pintype "passive"))
    )
  )
)
